# STPR_LMTSW_SRV.net
KiCad netlist of a schematic drawn in Altium Designer
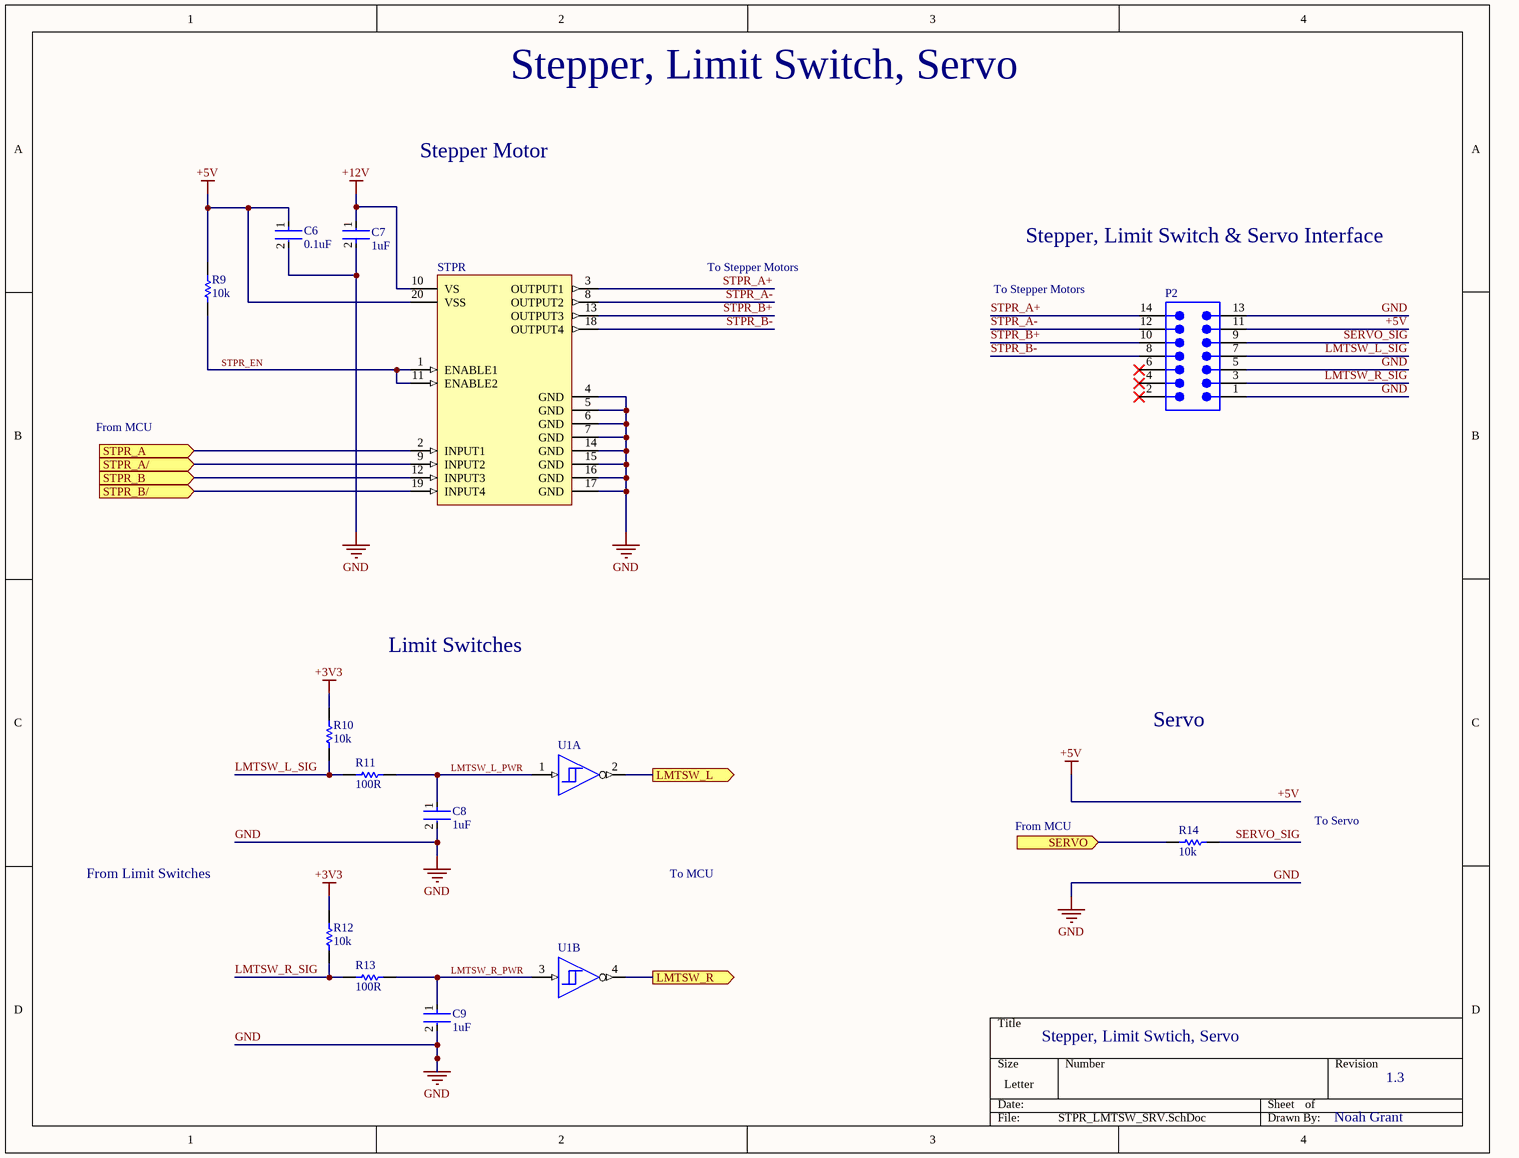
[diagram p0: STPR_LMTSW_SRV.SchDoc]

(export (version "E")
  (design (tool "Eeschema 10.0.6"))
  (components
    (comp (ref "C6")
      (value "0.1uF")
      (footprint "FP-CC0603-DA-MFG")
      (description "CAP CER 0.1UF 50V X7R 0603")
      (fields
        (field (name "MANUFACTURER") "YAGEO")
        (field (name "OCTOPART") "https://octopart.com/cc0603kpx7r9bb104-yageo-12885113")
      )
      (libsource (lib "Altium Content Vault") (part "11868f565c42a9108669ba33697ecf6"))
    )
    (comp (ref "C7")
      (value "1uF")
      (footprint "FP-C1608-080-0_1-MFG")
      (description "Multilayer Ceramic Capacitors 1μF ±10% 25V X6S SMD 0603")
      (fields (field (name "TOLERANCE") "10%"))
      (libsource (lib "Altium Content Vault") (part "236180d848d6139a670b325ea6854c9"))
    )
    (comp (ref "C8")
      (value "1uF")
      (footprint "FP-0603-L_1_6_0_1-W_0_8_0-IPC_A")
      (description "None")
      (fields (field (name "TOLERANCE") "10%"))
      (libsource (lib "Altium Content Vault") (part "02cd4be3c70576c341d710602a673aa"))
    )
    (comp (ref "C9")
      (value "1uF")
      (footprint "FP-0603-L_1_6_0_1-W_0_8_0-IPC_A")
      (description "None")
      (fields (field (name "TOLERANCE") "10%"))
      (libsource (lib "Altium Content Vault") (part "02cd4be3c70576c341d710602a673aa"))
    )
    (comp (ref "P2")
      (value "TSW-107-06-L-D")
      (footprint "SMTC-TSW-107-06-X-D")
      (description "0.025\" SQ Post Header, Through-hole, Vertical, -55 to 125 degC, 2.54 mm Pitch, 14-Pin, Male, RoHS")
      (fields (field (name "MANUFACTURER") "Samtec"))
      (libsource (lib "Altium Content Vault") (part "SMTC-TSW-107-X-X-D-X"))
    )
    (comp (ref "R9")
      (value "10k")
      (footprint "RESC1609X50X30NL8T20")
      (description "Chip Resistor, 10 KOhm, +/- 1%, 100 mW, -55 to 155 degC, 0603 (1608 Metric), RoHS, Tape and Reel")
      (fields (field (name "MANUFACTURER") "Vishay Semiconductor"))
      (libsource (lib "Altium Content Vault") (part "RES-2"))
    )
    (comp (ref "R10")
      (value "10k")
      (footprint "RESC1609X50X30NL8T20")
      (description "Chip Resistor, 10 KOhm, +/- 1%, 100 mW, -55 to 155 degC, 0603 (1608 Metric), RoHS, Tape and Reel")
      (fields (field (name "MANUFACTURER") "Vishay Semiconductor"))
      (libsource (lib "Altium Content Vault") (part "RES-2"))
    )
    (comp (ref "R11")
      (value "100R")
      (footprint "RESC1609X50X30ML8T20")
      (description "Chip Resistor, 100 Ohm, +/- 1%, 100 mW,-55 to 155 degC, 0603 (1608 Metric), RoHS, Tape and Ree")
      (fields (field (name "MANUFACTURER") "Vishay Semiconductor"))
      (libsource (lib "Altium Content Vault") (part "RES-2"))
    )
    (comp (ref "R12")
      (value "10k")
      (footprint "RESC1609X50X30NL8T20")
      (description "Chip Resistor, 10 KOhm, +/- 1%, 100 mW, -55 to 155 degC, 0603 (1608 Metric), RoHS, Tape and Reel")
      (fields (field (name "MANUFACTURER") "Vishay Semiconductor"))
      (libsource (lib "Altium Content Vault") (part "RES-2"))
    )
    (comp (ref "R13")
      (value "100R")
      (footprint "RESC1609X50X30ML8T20")
      (description "Chip Resistor, 100 Ohm, +/- 1%, 100 mW,-55 to 155 degC, 0603 (1608 Metric), RoHS, Tape and Ree")
      (fields (field (name "MANUFACTURER") "Vishay Semiconductor"))
      (libsource (lib "Altium Content Vault") (part "RES-2"))
    )
    (comp (ref "R14")
      (value "10k")
      (footprint "RESC1609X50X30NL8T20")
      (description "Chip Resistor, 10 KOhm, +/- 1%, 100 mW, -55 to 155 degC, 0603 (1608 Metric), RoHS, Tape and Reel")
      (fields (field (name "MANUFACTURER") "Vishay Semiconductor"))
      (libsource (lib "Altium Content Vault") (part "RES-2"))
    )
    (comp (ref "STPR")
      (value "L293DD")
      (footprint "STM-SOIC-20_M")
      (description "Push-Pull Four Channel Driver with Diodes, 4.5 to 36 V, 20-Pin SOIC, RoHS, Tube")
      (fields (field (name "TOLERANCE") "1%"))
      (libsource (lib "Altium Content Vault") (part "STM-L293DD-SO-20"))
    )
    (comp (ref "U1")
      (value "SN74HC14PWT")
      (footprint "PW0014A_M")
      (description "Hex Schmitt-Trigger Inverters, PW0014A, SMALL T&R")
      (fields
        (field (name "GENERIC PART NUMBER") "SN74HC14")
        (field (name "MANUFACTURER") "Texas Instruments")
      )
      (libsource (lib "Altium Content Vault") (part "TI-CD_SNX4XXXXXX4X_19A-14-SCHMITT"))
    )
  )
  (nets
    (net (code "1") (name "+3V3") (class "Default")
      (node (ref "R10") (pin "2") (pinfunction "2_2") (pintype "passive"))
      (node (ref "R12") (pin "2") (pinfunction "2_2") (pintype "passive"))
    )
    (net (code "2") (name "+5V") (class "Default")
      (node (ref "C6") (pin "1") (pinfunction "1_1") (pintype "passive"))
      (node (ref "P2") (pin "11") (pinfunction "11_11") (pintype "passive"))
      (node (ref "R9") (pin "2") (pinfunction "2_2") (pintype "passive"))
      (node (ref "STPR") (pin "20") (pinfunction "VSS_20") (pintype "power_in"))
    )
    (net (code "3") (name "+12V") (class "Default")
      (node (ref "C7") (pin "1") (pinfunction "1_1") (pintype "passive"))
      (node (ref "STPR") (pin "10") (pinfunction "VS_10") (pintype "power_in"))
    )
    (net (code "4") (name "/LMTSW_L") (class "Default")
      (node (ref "U1") (pin "2") (pinfunction "~{1Y}_2") (pintype "output"))
    )
    (net (code "5") (name "/LMTSW_L_PWR") (class "Default")
      (node (ref "C8") (pin "1") (pinfunction "1_1") (pintype "passive"))
      (node (ref "R11") (pin "1") (pinfunction "1_1") (pintype "passive"))
      (node (ref "U1") (pin "1") (pinfunction "1A_1") (pintype "input"))
    )
    (net (code "6") (name "/LMTSW_L_SIG") (class "Default")
      (node (ref "P2") (pin "7") (pinfunction "7_7") (pintype "passive"))
      (node (ref "R10") (pin "1") (pinfunction "1_1") (pintype "passive"))
      (node (ref "R11") (pin "2") (pinfunction "2_2") (pintype "passive"))
    )
    (net (code "7") (name "/LMTSW_R") (class "Default")
      (node (ref "U1") (pin "4") (pinfunction "~{2Y}_4") (pintype "output"))
    )
    (net (code "8") (name "/LMTSW_R_PWR") (class "Default")
      (node (ref "C9") (pin "1") (pinfunction "1_1") (pintype "passive"))
      (node (ref "R13") (pin "1") (pinfunction "1_1") (pintype "passive"))
      (node (ref "U1") (pin "3") (pinfunction "2A_3") (pintype "input"))
    )
    (net (code "9") (name "/LMTSW_R_SIG") (class "Default")
      (node (ref "P2") (pin "3") (pinfunction "3_3") (pintype "passive"))
      (node (ref "R12") (pin "1") (pinfunction "1_1") (pintype "passive"))
      (node (ref "R13") (pin "2") (pinfunction "2_2") (pintype "passive"))
    )
    (net (code "10") (name "/SERVO") (class "Default")
      (node (ref "R14") (pin "1") (pinfunction "1_1") (pintype "passive"))
    )
    (net (code "11") (name "/SERVO_SIG") (class "Default")
      (node (ref "P2") (pin "9") (pinfunction "9_9") (pintype "passive"))
      (node (ref "R14") (pin "2") (pinfunction "2_2") (pintype "passive"))
    )
    (net (code "12") (name "/STPR_A") (class "Default")
      (node (ref "STPR") (pin "2") (pinfunction "INPUT1_2") (pintype "input"))
    )
    (net (code "13") (name "/STPR_A+") (class "Default")
      (node (ref "P2") (pin "14") (pinfunction "14_14") (pintype "passive"))
      (node (ref "STPR") (pin "3") (pinfunction "OUTPUT1_3") (pintype "output"))
    )
    (net (code "14") (name "/STPR_A-") (class "Default")
      (node (ref "P2") (pin "12") (pinfunction "12_12") (pintype "passive"))
      (node (ref "STPR") (pin "8") (pinfunction "OUTPUT2_8") (pintype "output"))
    )
    (net (code "15") (name "/STPR_A{slash}") (class "Default")
      (node (ref "STPR") (pin "9") (pinfunction "INPUT2_9") (pintype "input"))
    )
    (net (code "16") (name "/STPR_B") (class "Default")
      (node (ref "STPR") (pin "12") (pinfunction "INPUT3_12") (pintype "input"))
    )
    (net (code "17") (name "/STPR_B+") (class "Default")
      (node (ref "P2") (pin "10") (pinfunction "10_10") (pintype "passive"))
      (node (ref "STPR") (pin "13") (pinfunction "OUTPUT3_13") (pintype "output"))
    )
    (net (code "18") (name "/STPR_B-") (class "Default")
      (node (ref "P2") (pin "8") (pinfunction "8_8") (pintype "passive"))
      (node (ref "STPR") (pin "18") (pinfunction "OUTPUT4_18") (pintype "output"))
    )
    (net (code "19") (name "/STPR_B{slash}") (class "Default")
      (node (ref "STPR") (pin "19") (pinfunction "INPUT4_19") (pintype "input"))
    )
    (net (code "20") (name "/STPR_EN") (class "Default")
      (node (ref "R9") (pin "1") (pinfunction "1_1") (pintype "passive"))
      (node (ref "STPR") (pin "1") (pinfunction "ENABLE1_1") (pintype "input"))
      (node (ref "STPR") (pin "11") (pinfunction "ENABLE2_11") (pintype "input"))
    )
    (net (code "21") (name "GND") (class "Default")
      (node (ref "C6") (pin "2") (pinfunction "2_2") (pintype "passive"))
      (node (ref "C7") (pin "2") (pinfunction "2_2") (pintype "passive"))
      (node (ref "C8") (pin "2") (pinfunction "2_2") (pintype "passive"))
      (node (ref "C9") (pin "2") (pinfunction "2_2") (pintype "passive"))
      (node (ref "P2") (pin "1") (pinfunction "1_1") (pintype "passive"))
      (node (ref "P2") (pin "13") (pinfunction "13_13") (pintype "passive"))
      (node (ref "P2") (pin "5") (pinfunction "5_5") (pintype "passive"))
      (node (ref "STPR") (pin "14") (pinfunction "GND_14") (pintype "power_in"))
      (node (ref "STPR") (pin "15") (pinfunction "GND_15") (pintype "power_in"))
      (node (ref "STPR") (pin "16") (pinfunction "GND_16") (pintype "power_in"))
      (node (ref "STPR") (pin "17") (pinfunction "GND_17") (pintype "power_in"))
      (node (ref "STPR") (pin "4") (pinfunction "GND_4") (pintype "power_in"))
      (node (ref "STPR") (pin "5") (pinfunction "GND_5") (pintype "power_in"))
      (node (ref "STPR") (pin "6") (pinfunction "GND_6") (pintype "power_in"))
      (node (ref "STPR") (pin "7") (pinfunction "GND_7") (pintype "power_in"))
    )
    (net (code "22") (name "unconnected-(P2-Pad2)") (class "Default")
      (node (ref "P2") (pin "2") (pinfunction "2_2") (pintype "passive+no_connect"))
    )
    (net (code "23") (name "unconnected-(P2-Pad4)") (class "Default")
      (node (ref "P2") (pin "4") (pinfunction "4_4") (pintype "passive+no_connect"))
    )
    (net (code "24") (name "unconnected-(P2-Pad6)") (class "Default")
      (node (ref "P2") (pin "6") (pinfunction "6_6") (pintype "passive+no_connect"))
    )
  )
)
